# Mixer-Analog-OPA2134-Rev-J.net
KiCad netlist of a schematic drawn in EAGLE
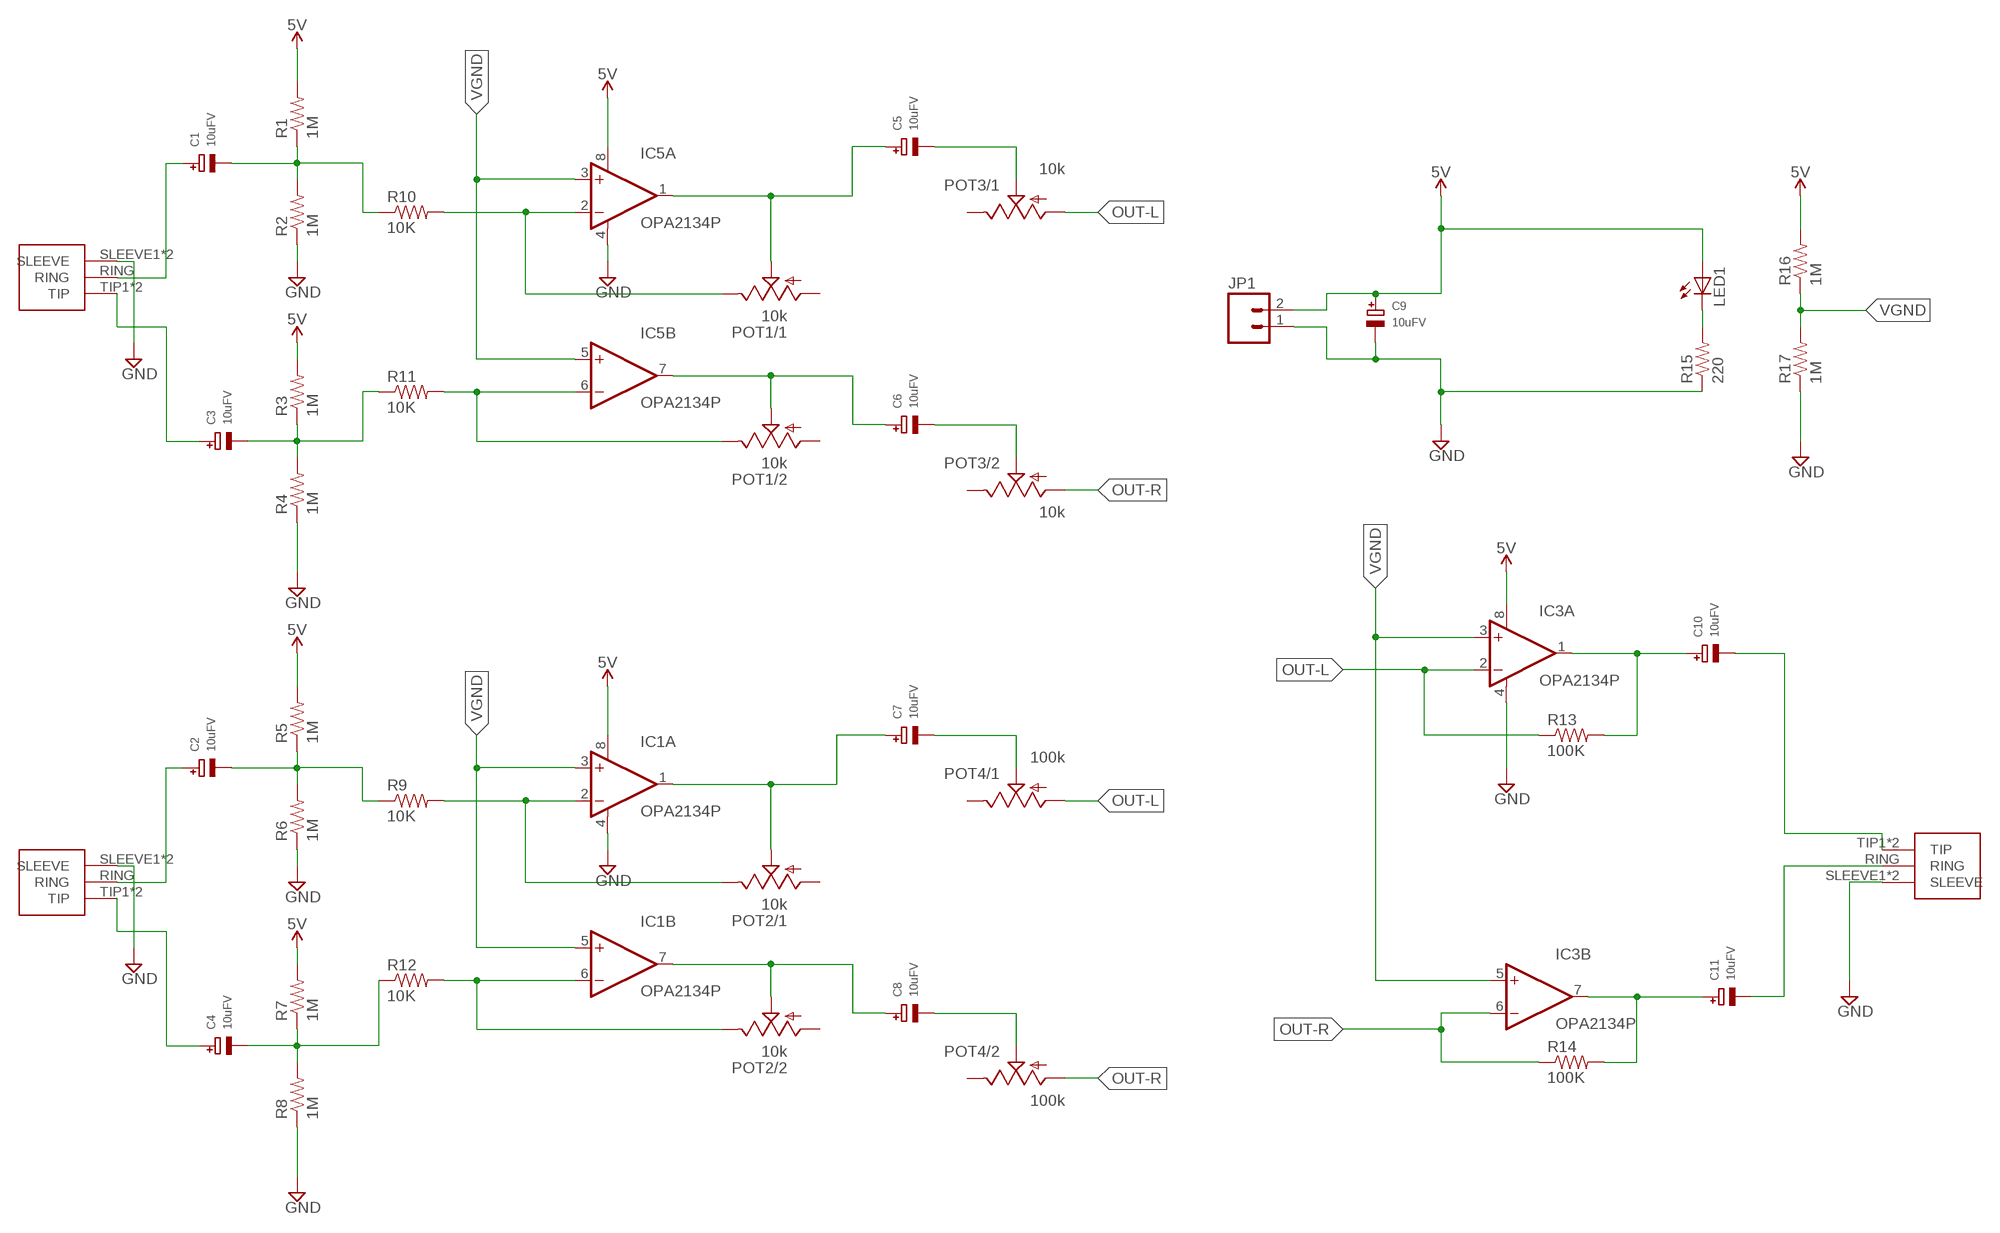
[diagram p0: schematic, sheet 1]

(export (version "E")
  (design (tool "Eeschema 10.0.6"))
  (components
    (comp (ref "C1")
      (value "10uFV")
      (footprint "eagle-import:CELEC_3.5MM_8MM")
      (libsource (lib "eagle-import") (part "CAP_ELECTROLYTICPTH_3.5MMGRID_8MMDIA"))
    )
    (comp (ref "C2")
      (value "10uFV")
      (footprint "eagle-import:CELEC_3.5MM_8MM")
      (libsource (lib "eagle-import") (part "CAP_ELECTROLYTICPTH_3.5MMGRID_8MMDIA"))
    )
    (comp (ref "C3")
      (value "10uFV")
      (footprint "eagle-import:CELEC_3.5MM_8MM")
      (libsource (lib "eagle-import") (part "CAP_ELECTROLYTICPTH_3.5MMGRID_8MMDIA"))
    )
    (comp (ref "C4")
      (value "10uFV")
      (footprint "eagle-import:CELEC_3.5MM_8MM")
      (libsource (lib "eagle-import") (part "CAP_ELECTROLYTICPTH_3.5MMGRID_8MMDIA"))
    )
    (comp (ref "C5")
      (value "10uFV")
      (footprint "eagle-import:CELEC_3.5MM_8MM")
      (libsource (lib "eagle-import") (part "CAP_ELECTROLYTICPTH_3.5MMGRID_8MMDIA"))
    )
    (comp (ref "C6")
      (value "10uFV")
      (footprint "eagle-import:CELEC_3.5MM_8MM")
      (libsource (lib "eagle-import") (part "CAP_ELECTROLYTICPTH_3.5MMGRID_8MMDIA"))
    )
    (comp (ref "C7")
      (value "10uFV")
      (footprint "eagle-import:CELEC_3.5MM_8MM")
      (libsource (lib "eagle-import") (part "CAP_ELECTROLYTICPTH_3.5MMGRID_8MMDIA"))
    )
    (comp (ref "C8")
      (value "10uFV")
      (footprint "eagle-import:CELEC_3.5MM_8MM")
      (libsource (lib "eagle-import") (part "CAP_ELECTROLYTICPTH_3.5MMGRID_8MMDIA"))
    )
    (comp (ref "C9")
      (value "10uFV")
      (footprint "eagle-import:CELEC_3.5MM_8MM")
      (libsource (lib "eagle-import") (part "CAP_ELECTROLYTICPTH_3.5MMGRID_8MMDIA"))
    )
    (comp (ref "C10")
      (value "10uFV")
      (footprint "eagle-import:CELEC_3.5MM_8MM")
      (libsource (lib "eagle-import") (part "CAP_ELECTROLYTICPTH_3.5MMGRID_8MMDIA"))
    )
    (comp (ref "C11")
      (value "10uFV")
      (footprint "eagle-import:CELEC_3.5MM_8MM")
      (libsource (lib "eagle-import") (part "CAP_ELECTROLYTICPTH_3.5MMGRID_8MMDIA"))
    )
    (comp (ref "IC1")
      (value "OPA2134P")
      (footprint "eagle-import:DIL08")
      (fields (field (name "MF") "TEXAS INSTRUMENTS") (field (name "MPN") "OPA2134PA"))
      (libsource (lib "eagle-import") (part "OPA2134P"))
    )
    (comp (ref "IC3")
      (value "OPA2134P")
      (footprint "eagle-import:DIL08")
      (fields (field (name "MF") "TEXAS INSTRUMENTS") (field (name "MPN") "OPA2134PA"))
      (libsource (lib "eagle-import") (part "OPA2134P"))
    )
    (comp (ref "IC5")
      (value "OPA2134P")
      (footprint "eagle-import:DIL08")
      (fields (field (name "MF") "TEXAS INSTRUMENTS") (field (name "MPN") "OPA2134PA"))
      (libsource (lib "eagle-import") (part "OPA2134P"))
    )
    (comp (ref "J1")
      (value "1/8\"-F-STEREO-PCB")
      (footprint "eagle-import:1_8_-F-STEREO-PCB")
      (libsource (lib "eagle-import") (part "1/8{dblquote}-F-STEREO-PCB"))
    )
    (comp (ref "J2")
      (value "1/8\"-F-STEREO-PCB")
      (footprint "eagle-import:1_8_-F-STEREO-PCB")
      (libsource (lib "eagle-import") (part "1/8{dblquote}-F-STEREO-PCB"))
    )
    (comp (ref "J3")
      (value "1/8\"-F-STEREO-PCB")
      (footprint "eagle-import:1_8_-F-STEREO-PCB")
      (libsource (lib "eagle-import") (part "1/8{dblquote}-F-STEREO-PCB"))
    )
    (comp (ref "JP1")
      (value "M02LOCK")
      (footprint "eagle-import:1X02_LOCK")
      (libsource (lib "eagle-import") (part "M02LOCK"))
    )
    (comp (ref "LED1")
      (value "LED3MM")
      (footprint "eagle-import:LED3MM")
      (libsource (lib "eagle-import") (part "LED3MM"))
    )
    (comp (ref "POT1")
      (value "10k")
      (footprint "eagle-import:PTV112")
      (fields (field (name "MF") "STMicroelectronics") (field (name "MP") "PTV112"))
      (libsource (lib "eagle-import") (part "POT-DUAL-PTV112-4420"))
    )
    (comp (ref "POT2")
      (value "10k")
      (footprint "eagle-import:PTV112")
      (fields (field (name "MF") "STMicroelectronics") (field (name "MP") "PTV112"))
      (libsource (lib "eagle-import") (part "POT-DUAL-PTV112-4420"))
    )
    (comp (ref "POT3")
      (value "10k")
      (footprint "eagle-import:PTV112")
      (fields
        (field (name "MF") "STMicroelectronics")
        (field (name "MP") "PTV112")
        (field (name "SPICEPREFIX") "J")
      )
      (libsource (lib "eagle-import") (part "POT-DUAL-PTV112-4420"))
    )
    (comp (ref "POT4")
      (value "100k")
      (footprint "eagle-import:PTV112")
      (fields
        (field (name "MF") "STMicroelectronics")
        (field (name "MP") "PTV112")
        (field (name "SPICEPREFIX") "J")
      )
      (libsource (lib "eagle-import") (part "POT-DUAL-PTV112-4420"))
    )
    (comp (ref "R1")
      (value "1M")
      (footprint "eagle-import:AXIAL-0.3EZ")
      (fields (field (name "SPICEPREFIX") "R"))
      (libsource (lib "eagle-import") (part "RESISTOREZ"))
    )
    (comp (ref "R2")
      (value "1M")
      (footprint "eagle-import:AXIAL-0.3")
      (fields (field (name "SPICEPREFIX") "R"))
      (libsource (lib "eagle-import") (part "RESISTORAXIAL-0.3"))
    )
    (comp (ref "R3")
      (value "1M")
      (footprint "eagle-import:AXIAL-0.3EZ")
      (fields (field (name "SPICEPREFIX") "R"))
      (libsource (lib "eagle-import") (part "RESISTOREZ"))
    )
    (comp (ref "R4")
      (value "1M")
      (footprint "eagle-import:AXIAL-0.3EZ")
      (fields (field (name "SPICEPREFIX") "R"))
      (libsource (lib "eagle-import") (part "RESISTOREZ"))
    )
    (comp (ref "R5")
      (value "1M")
      (footprint "eagle-import:AXIAL-0.3EZ")
      (fields (field (name "SPICEPREFIX") "R"))
      (libsource (lib "eagle-import") (part "RESISTOREZ"))
    )
    (comp (ref "R6")
      (value "1M")
      (footprint "eagle-import:AXIAL-0.3EZ")
      (fields (field (name "SPICEPREFIX") "R"))
      (libsource (lib "eagle-import") (part "RESISTOREZ"))
    )
    (comp (ref "R7")
      (value "1M")
      (footprint "eagle-import:AXIAL-0.3EZ")
      (fields (field (name "SPICEPREFIX") "R"))
      (libsource (lib "eagle-import") (part "RESISTOREZ"))
    )
    (comp (ref "R8")
      (value "1M")
      (footprint "eagle-import:AXIAL-0.3EZ")
      (fields (field (name "SPICEPREFIX") "R"))
      (libsource (lib "eagle-import") (part "RESISTOREZ"))
    )
    (comp (ref "R9")
      (value "10K")
      (footprint "eagle-import:AXIAL-0.3EZ")
      (fields (field (name "SPICEPREFIX") "R"))
      (libsource (lib "eagle-import") (part "RESISTOREZ"))
    )
    (comp (ref "R10")
      (value "10K")
      (footprint "eagle-import:AXIAL-0.3EZ")
      (fields (field (name "SPICEPREFIX") "R"))
      (libsource (lib "eagle-import") (part "RESISTOREZ"))
    )
    (comp (ref "R11")
      (value "10K")
      (footprint "eagle-import:AXIAL-0.3EZ")
      (fields (field (name "SPICEPREFIX") "R"))
      (libsource (lib "eagle-import") (part "RESISTOREZ"))
    )
    (comp (ref "R12")
      (value "10K")
      (footprint "eagle-import:AXIAL-0.3EZ")
      (fields (field (name "SPICEPREFIX") "R"))
      (libsource (lib "eagle-import") (part "RESISTOREZ"))
    )
    (comp (ref "R13")
      (value "100K")
      (footprint "eagle-import:AXIAL-0.3EZ")
      (fields (field (name "SPICEPREFIX") "R"))
      (libsource (lib "eagle-import") (part "RESISTOREZ"))
    )
    (comp (ref "R14")
      (value "100K")
      (footprint "eagle-import:AXIAL-0.3EZ")
      (fields (field (name "SPICEPREFIX") "R"))
      (libsource (lib "eagle-import") (part "RESISTOREZ"))
    )
    (comp (ref "R15")
      (value "220")
      (footprint "eagle-import:AXIAL-0.3EZ")
      (libsource (lib "eagle-import") (part "RESISTOREZ"))
    )
    (comp (ref "R16")
      (value "1M")
      (footprint "eagle-import:AXIAL-0.3EZ")
      (libsource (lib "eagle-import") (part "RESISTOREZ"))
    )
    (comp (ref "R17")
      (value "1M")
      (footprint "eagle-import:AXIAL-0.3EZ")
      (libsource (lib "eagle-import") (part "RESISTOREZ"))
    )
  )
  (nets
    (net (code "1") (name "5V") (class "Default")
      (node (ref "C9") (pin "+") (pinfunction "+_+") (pintype "passive"))
      (node (ref "IC1") (pin "8") (pinfunction "V+_8") (pintype "power_in"))
      (node (ref "IC3") (pin "8") (pinfunction "V+_8") (pintype "power_in"))
      (node (ref "IC5") (pin "8") (pinfunction "V+_8") (pintype "power_in"))
      (node (ref "JP1") (pin "2") (pinfunction "2_2") (pintype "passive"))
      (node (ref "LED1") (pin "A") (pinfunction "A_A") (pintype "passive"))
      (node (ref "R1") (pin "P$2") (pinfunction "2_P$2") (pintype "passive"))
      (node (ref "R16") (pin "P$2") (pinfunction "2_P$2") (pintype "passive"))
      (node (ref "R3") (pin "P$2") (pinfunction "2_P$2") (pintype "passive"))
      (node (ref "R5") (pin "P$2") (pinfunction "2_P$2") (pintype "passive"))
      (node (ref "R7") (pin "P$2") (pinfunction "2_P$2") (pintype "passive"))
    )
    (net (code "2") (name "GND") (class "Default")
      (node (ref "C9") (pin "-") (pinfunction "-_-") (pintype "passive"))
      (node (ref "IC1") (pin "4") (pinfunction "V-_4") (pintype "power_in"))
      (node (ref "IC3") (pin "4") (pinfunction "V-_4") (pintype "power_in"))
      (node (ref "IC5") (pin "4") (pinfunction "V-_4") (pintype "power_in"))
      (node (ref "J1") (pin "SLEEVE1") (pinfunction "SLEEVE_SLEEVE1") (pintype "bidirectional"))
      (node (ref "J1") (pin "SLEEVE2") (pinfunction "SLEEVE_SLEEVE2") (pintype "bidirectional"))
      (node (ref "J2") (pin "SLEEVE1") (pinfunction "SLEEVE_SLEEVE1") (pintype "bidirectional"))
      (node (ref "J2") (pin "SLEEVE2") (pinfunction "SLEEVE_SLEEVE2") (pintype "bidirectional"))
      (node (ref "J3") (pin "SLEEVE1") (pinfunction "SLEEVE_SLEEVE1") (pintype "bidirectional"))
      (node (ref "J3") (pin "SLEEVE2") (pinfunction "SLEEVE_SLEEVE2") (pintype "bidirectional"))
      (node (ref "JP1") (pin "1") (pinfunction "1_1") (pintype "passive"))
      (node (ref "R15") (pin "P$1") (pinfunction "1_P$1") (pintype "passive"))
      (node (ref "R17") (pin "P$1") (pinfunction "1_P$1") (pintype "passive"))
      (node (ref "R2") (pin "P$1") (pinfunction "1_P$1") (pintype "passive"))
      (node (ref "R4") (pin "P$1") (pinfunction "1_P$1") (pintype "passive"))
      (node (ref "R6") (pin "P$1") (pinfunction "1_P$1") (pintype "passive"))
      (node (ref "R8") (pin "P$1") (pinfunction "1_P$1") (pintype "passive"))
    )
    (net (code "3") (name "Net-(C1-Pad+)") (class "Default")
      (node (ref "C1") (pin "+") (pinfunction "+_+") (pintype "passive"))
      (node (ref "J1") (pin "RING") (pinfunction "RING_RING") (pintype "bidirectional"))
    )
    (net (code "4") (name "Net-(C2-Pad+)") (class "Default")
      (node (ref "C2") (pin "+") (pinfunction "+_+") (pintype "passive"))
      (node (ref "J2") (pin "RING") (pinfunction "RING_RING") (pintype "bidirectional"))
    )
    (net (code "5") (name "Net-(C3-Pad+)") (class "Default")
      (node (ref "C3") (pin "+") (pinfunction "+_+") (pintype "passive"))
      (node (ref "J1") (pin "TIP1") (pinfunction "TIP_TIP1") (pintype "bidirectional"))
      (node (ref "J1") (pin "TIP2") (pinfunction "TIP_TIP2") (pintype "bidirectional"))
    )
    (net (code "6") (name "Net-(C4-Pad+)") (class "Default")
      (node (ref "C4") (pin "+") (pinfunction "+_+") (pintype "passive"))
      (node (ref "J2") (pin "TIP1") (pinfunction "TIP_TIP1") (pintype "bidirectional"))
      (node (ref "J2") (pin "TIP2") (pinfunction "TIP_TIP2") (pintype "bidirectional"))
    )
    (net (code "7") (name "Net-(C10-Pad-)") (class "Default")
      (node (ref "C10") (pin "-") (pinfunction "-_-") (pintype "passive"))
      (node (ref "J3") (pin "TIP1") (pinfunction "TIP_TIP1") (pintype "bidirectional"))
      (node (ref "J3") (pin "TIP2") (pinfunction "TIP_TIP2") (pintype "bidirectional"))
    )
    (net (code "8") (name "Net-(C11-Pad-)") (class "Default")
      (node (ref "C11") (pin "-") (pinfunction "-_-") (pintype "passive"))
      (node (ref "J3") (pin "RING") (pinfunction "RING_RING") (pintype "bidirectional"))
    )
    (net (code "9") (name "Net-(IC1A--IN)") (class "Default")
      (node (ref "IC1") (pin "2") (pinfunction "-IN_2") (pintype "input"))
      (node (ref "POT2") (pin "1.3") (pinfunction "E_1.3") (pintype "passive"))
      (node (ref "R9") (pin "P$2") (pinfunction "2_P$2") (pintype "passive"))
    )
    (net (code "10") (name "Net-(IC1A-OUT)") (class "Default")
      (node (ref "C7") (pin "+") (pinfunction "+_+") (pintype "passive"))
      (node (ref "IC1") (pin "1") (pinfunction "OUT_1") (pintype "output"))
      (node (ref "POT2") (pin "1.2") (pinfunction "S_1.2") (pintype "passive"))
    )
    (net (code "11") (name "Net-(IC1B--IN)") (class "Default")
      (node (ref "IC1") (pin "6") (pinfunction "-IN_6") (pintype "input"))
      (node (ref "POT2") (pin "2.3") (pinfunction "E_2.3") (pintype "passive"))
      (node (ref "R12") (pin "P$2") (pinfunction "2_P$2") (pintype "passive"))
    )
    (net (code "12") (name "Net-(IC1B-OUT)") (class "Default")
      (node (ref "C8") (pin "+") (pinfunction "+_+") (pintype "passive"))
      (node (ref "IC1") (pin "7") (pinfunction "OUT_7") (pintype "output"))
      (node (ref "POT2") (pin "2.2") (pinfunction "S_2.2") (pintype "passive"))
    )
    (net (code "13") (name "Net-(IC3A-OUT)") (class "Default")
      (node (ref "C10") (pin "+") (pinfunction "+_+") (pintype "passive"))
      (node (ref "IC3") (pin "1") (pinfunction "OUT_1") (pintype "output"))
      (node (ref "R13") (pin "P$2") (pinfunction "2_P$2") (pintype "passive"))
    )
    (net (code "14") (name "Net-(IC3B-OUT)") (class "Default")
      (node (ref "C11") (pin "+") (pinfunction "+_+") (pintype "passive"))
      (node (ref "IC3") (pin "7") (pinfunction "OUT_7") (pintype "output"))
      (node (ref "R14") (pin "P$2") (pinfunction "2_P$2") (pintype "passive"))
    )
    (net (code "15") (name "Net-(IC5A--IN)") (class "Default")
      (node (ref "IC5") (pin "2") (pinfunction "-IN_2") (pintype "input"))
      (node (ref "POT1") (pin "1.3") (pinfunction "E_1.3") (pintype "passive"))
      (node (ref "R10") (pin "P$2") (pinfunction "2_P$2") (pintype "passive"))
    )
    (net (code "16") (name "Net-(IC5A-OUT)") (class "Default")
      (node (ref "C5") (pin "+") (pinfunction "+_+") (pintype "passive"))
      (node (ref "IC5") (pin "1") (pinfunction "OUT_1") (pintype "output"))
      (node (ref "POT1") (pin "1.2") (pinfunction "S_1.2") (pintype "passive"))
    )
    (net (code "17") (name "Net-(IC5B--IN)") (class "Default")
      (node (ref "IC5") (pin "6") (pinfunction "-IN_6") (pintype "input"))
      (node (ref "POT1") (pin "2.3") (pinfunction "E_2.3") (pintype "passive"))
      (node (ref "R11") (pin "P$2") (pinfunction "2_P$2") (pintype "passive"))
    )
    (net (code "18") (name "Net-(IC5B-OUT)") (class "Default")
      (node (ref "C6") (pin "+") (pinfunction "+_+") (pintype "passive"))
      (node (ref "IC5") (pin "7") (pinfunction "OUT_7") (pintype "output"))
      (node (ref "POT1") (pin "2.2") (pinfunction "S_2.2") (pintype "passive"))
    )
    (net (code "19") (name "Net-(LED1-C)") (class "Default")
      (node (ref "LED1") (pin "K") (pinfunction "C_K") (pintype "passive"))
      (node (ref "R15") (pin "P$2") (pinfunction "2_P$2") (pintype "passive"))
    )
    (net (code "20") (name "Net-(POT3A-S)") (class "Default")
      (node (ref "C5") (pin "-") (pinfunction "-_-") (pintype "passive"))
      (node (ref "POT3") (pin "1.2") (pinfunction "S_1.2") (pintype "passive"))
    )
    (net (code "21") (name "Net-(POT3B-S)") (class "Default")
      (node (ref "C6") (pin "-") (pinfunction "-_-") (pintype "passive"))
      (node (ref "POT3") (pin "2.2") (pinfunction "S_2.2") (pintype "passive"))
    )
    (net (code "22") (name "Net-(POT4A-S)") (class "Default")
      (node (ref "C7") (pin "-") (pinfunction "-_-") (pintype "passive"))
      (node (ref "POT4") (pin "1.2") (pinfunction "S_1.2") (pintype "passive"))
    )
    (net (code "23") (name "Net-(POT4B-S)") (class "Default")
      (node (ref "C8") (pin "-") (pinfunction "-_-") (pintype "passive"))
      (node (ref "POT4") (pin "2.2") (pinfunction "S_2.2") (pintype "passive"))
    )
    (net (code "24") (name "Net-(R1-1)") (class "Default")
      (node (ref "C1") (pin "-") (pinfunction "-_-") (pintype "passive"))
      (node (ref "R1") (pin "P$1") (pinfunction "1_P$1") (pintype "passive"))
      (node (ref "R10") (pin "P$1") (pinfunction "1_P$1") (pintype "passive"))
      (node (ref "R2") (pin "P$2") (pinfunction "2_P$2") (pintype "passive"))
    )
    (net (code "25") (name "Net-(R5-1)") (class "Default")
      (node (ref "C2") (pin "-") (pinfunction "-_-") (pintype "passive"))
      (node (ref "R5") (pin "P$1") (pinfunction "1_P$1") (pintype "passive"))
      (node (ref "R6") (pin "P$2") (pinfunction "2_P$2") (pintype "passive"))
      (node (ref "R9") (pin "P$1") (pinfunction "1_P$1") (pintype "passive"))
    )
    (net (code "26") (name "Net-(R11-1)") (class "Default")
      (node (ref "C3") (pin "-") (pinfunction "-_-") (pintype "passive"))
      (node (ref "R11") (pin "P$1") (pinfunction "1_P$1") (pintype "passive"))
      (node (ref "R3") (pin "P$1") (pinfunction "1_P$1") (pintype "passive"))
      (node (ref "R4") (pin "P$2") (pinfunction "2_P$2") (pintype "passive"))
    )
    (net (code "27") (name "Net-(R12-1)") (class "Default")
      (node (ref "C4") (pin "-") (pinfunction "-_-") (pintype "passive"))
      (node (ref "R12") (pin "P$1") (pinfunction "1_P$1") (pintype "passive"))
      (node (ref "R7") (pin "P$1") (pinfunction "1_P$1") (pintype "passive"))
      (node (ref "R8") (pin "P$2") (pinfunction "2_P$2") (pintype "passive"))
    )
    (net (code "28") (name "OUT-L") (class "Default")
      (node (ref "IC3") (pin "2") (pinfunction "-IN_2") (pintype "input"))
      (node (ref "POT3") (pin "1.1") (pinfunction "A_1.1") (pintype "passive"))
      (node (ref "POT4") (pin "1.1") (pinfunction "A_1.1") (pintype "passive"))
      (node (ref "R13") (pin "P$1") (pinfunction "1_P$1") (pintype "passive"))
    )
    (net (code "29") (name "OUT-R") (class "Default")
      (node (ref "IC3") (pin "6") (pinfunction "-IN_6") (pintype "input"))
      (node (ref "POT3") (pin "2.1") (pinfunction "A_2.1") (pintype "passive"))
      (node (ref "POT4") (pin "2.1") (pinfunction "A_2.1") (pintype "passive"))
      (node (ref "R14") (pin "P$1") (pinfunction "1_P$1") (pintype "passive"))
    )
    (net (code "30") (name "VGND") (class "Default")
      (node (ref "IC1") (pin "3") (pinfunction "+IN_3") (pintype "input"))
      (node (ref "IC1") (pin "5") (pinfunction "+IN_5") (pintype "input"))
      (node (ref "IC3") (pin "3") (pinfunction "+IN_3") (pintype "input"))
      (node (ref "IC3") (pin "5") (pinfunction "+IN_5") (pintype "input"))
      (node (ref "IC5") (pin "3") (pinfunction "+IN_3") (pintype "input"))
      (node (ref "IC5") (pin "5") (pinfunction "+IN_5") (pintype "input"))
      (node (ref "R16") (pin "P$1") (pinfunction "1_P$1") (pintype "passive"))
      (node (ref "R17") (pin "P$2") (pinfunction "2_P$2") (pintype "passive"))
    )
    (net (code "31") (name "unconnected-(POT1A-A-Pad1.1)") (class "Default")
      (node (ref "POT1") (pin "1.1") (pinfunction "A_1.1") (pintype "passive"))
    )
    (net (code "32") (name "unconnected-(POT1B-A-Pad2.1)") (class "Default")
      (node (ref "POT1") (pin "2.1") (pinfunction "A_2.1") (pintype "passive"))
    )
    (net (code "33") (name "unconnected-(POT2A-A-Pad1.1)") (class "Default")
      (node (ref "POT2") (pin "1.1") (pinfunction "A_1.1") (pintype "passive"))
    )
    (net (code "34") (name "unconnected-(POT2B-A-Pad2.1)") (class "Default")
      (node (ref "POT2") (pin "2.1") (pinfunction "A_2.1") (pintype "passive"))
    )
    (net (code "35") (name "unconnected-(POT3A-E-Pad1.3)") (class "Default")
      (node (ref "POT3") (pin "1.3") (pinfunction "E_1.3") (pintype "passive"))
    )
    (net (code "36") (name "unconnected-(POT3B-E-Pad2.3)") (class "Default")
      (node (ref "POT3") (pin "2.3") (pinfunction "E_2.3") (pintype "passive"))
    )
    (net (code "37") (name "unconnected-(POT4A-E-Pad1.3)") (class "Default")
      (node (ref "POT4") (pin "1.3") (pinfunction "E_1.3") (pintype "passive"))
    )
    (net (code "38") (name "unconnected-(POT4B-E-Pad2.3)") (class "Default")
      (node (ref "POT4") (pin "2.3") (pinfunction "E_2.3") (pintype "passive"))
    )
  )
)
